# Y9A_4.net
KiCad netlist of a schematic drawn in Altium Designer
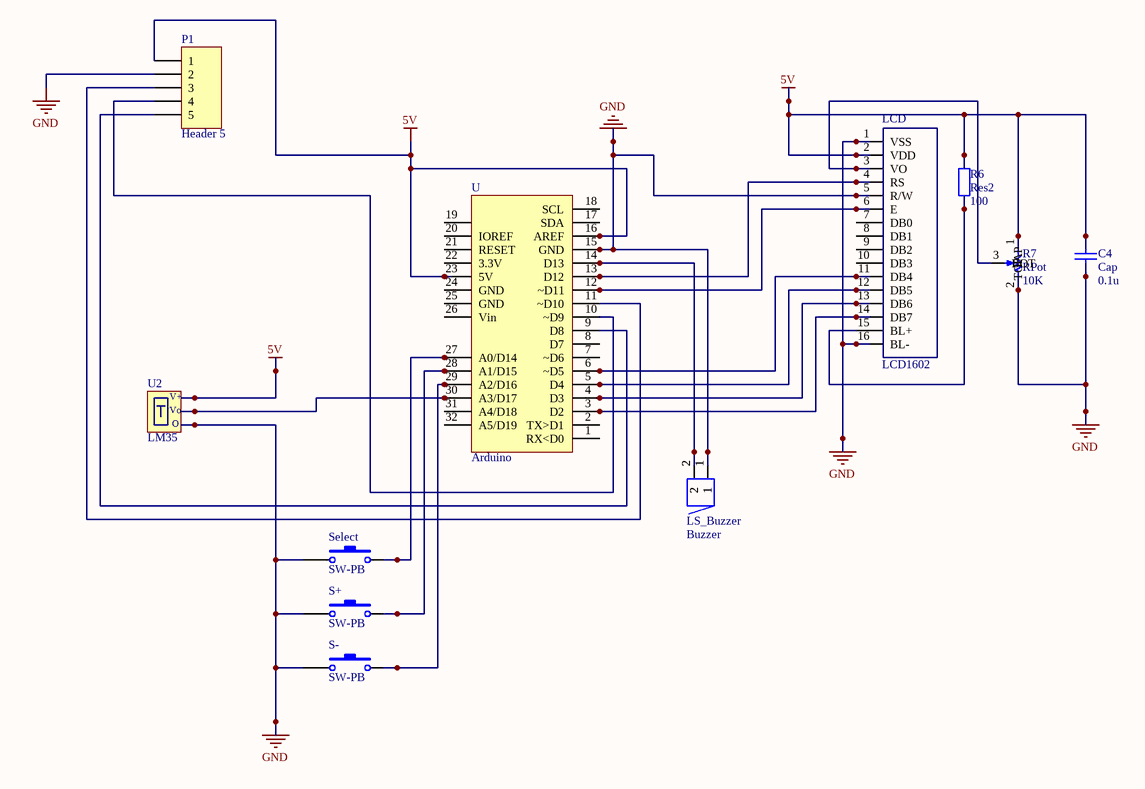
[diagram p0: Y9A_4.SchDoc]

(export (version "E")
  (design (tool "Eeschema 10.0.6"))
  (components
    (comp (ref "C4")
      (value "Cap")
      (footprint "RAD-0.3")
      (description "Capacitor")
      (fields (field (name "ALTIUM_VALUE") "0.1u") (field (name "PUBLISHER") "Altium Limited"))
      (libsource (lib "Miscellaneous Devices") (part "Cap"))
    )
    (comp (ref "LCD") (value "LCD1602") (footprint "LCD1602") (libsource (lib "LCD") (part "LCD1602")))
    (comp (ref "LS_Buzzer")
      (value "Buzzer")
      (footprint "Buzzer")
      (description "Magnetic Transducer Buzzer")
      (fields (field (name "PUBLISHER") "Altium Limited"))
      (libsource (lib "Miscellaneous Devices") (part "Buzzer"))
    )
    (comp (ref "P1")
      (value "Header 5")
      (footprint "HDR1X5")
      (description "Header, 5-Pin")
      (fields (field (name "PUBLISHER") "Altium Limited"))
      (libsource (lib "Miscellaneous Connectors") (part "Header 5"))
    )
    (comp (ref "R6")
      (value "Res2")
      (footprint "AXIAL-0.4")
      (description "Resistor")
      (fields (field (name "ALTIUM_VALUE") "100") (field (name "PUBLISHER") "Altium Limited"))
      (libsource (lib "Miscellaneous Devices") (part "Res2"))
    )
    (comp (ref "R7")
      (value "RPot")
      (footprint "RP-W")
      (description "Potentiometer")
      (fields (field (name "ALTIUM_VALUE") "10K") (field (name "PUBLISHER") "Altium Limited"))
      (libsource (lib "Miscellaneous Devices") (part "RPot"))
    )
    (comp (ref "S+")
      (value "SW-PB")
      (footprint "AN-S")
      (description "Switch")
      (fields (field (name "PUBLISHER") "Altium Limited"))
      (libsource (lib "Miscellaneous Devices") (part "SW-PB"))
    )
    (comp (ref "S-")
      (value "SW-PB")
      (footprint "AN-S")
      (description "Switch")
      (fields (field (name "PUBLISHER") "Altium Limited"))
      (libsource (lib "Miscellaneous Devices") (part "SW-PB"))
    )
    (comp (ref "Select")
      (value "SW-PB")
      (footprint "AN-S")
      (description "Switch")
      (fields (field (name "PUBLISHER") "Altium Limited"))
      (libsource (lib "Miscellaneous Devices") (part "SW-PB"))
    )
    (comp (ref "U")
      (value "Arduino")
      (footprint "Arduino-UNO-EX")
      (libsource (lib "LixhSch-N") (part "Arduino-UNO-EX"))
    )
    (comp (ref "U2")
      (value "LM35")
      (footprint "LM35")
      (description "LM35温度传感器")
      (libsource (lib "LixhSch") (part "LM35"))
    )
  )
  (nets
    (net (code "1") (name "5V") (class "Default")
      (node (ref "C4") (pin "2") (pinfunction "2_2") (pintype "passive"))
      (node (ref "LCD") (pin "2") (pinfunction "VDD_2") (pintype "passive"))
      (node (ref "P1") (pin "1") (pinfunction "1_1") (pintype "passive"))
      (node (ref "R6") (pin "2") (pinfunction "2_2") (pintype "passive"))
      (node (ref "R7") (pin "1") (pinfunction "TOP_1") (pintype "passive"))
      (node (ref "U") (pin "16") (pinfunction "AREF_16") (pintype "power_in"))
      (node (ref "U") (pin "23") (pinfunction "5V_23") (pintype "power_in"))
      (node (ref "U2") (pin "1") (pinfunction "1_1") (pintype "power_in"))
    )
    (net (code "2") (name "GND") (class "Default")
      (node (ref "C4") (pin "1") (pinfunction "1_1") (pintype "passive"))
      (node (ref "LCD") (pin "1") (pinfunction "VSS_1") (pintype "passive"))
      (node (ref "LCD") (pin "16") (pinfunction "BL-_16") (pintype "passive"))
      (node (ref "LCD") (pin "5") (pinfunction "R/W_5") (pintype "passive"))
      (node (ref "LS_Buzzer") (pin "1") (pinfunction "1_1") (pintype "passive"))
      (node (ref "P1") (pin "2") (pinfunction "2_2") (pintype "passive"))
      (node (ref "R7") (pin "2") (pinfunction "TAP_2") (pintype "passive"))
      (node (ref "S+") (pin "1") (pinfunction "1_1") (pintype "passive"))
      (node (ref "S-") (pin "1") (pinfunction "1_1") (pintype "passive"))
      (node (ref "Select") (pin "1") (pinfunction "1_1") (pintype "passive"))
      (node (ref "U") (pin "15") (pinfunction "GND_15") (pintype "power_in"))
      (node (ref "U2") (pin "3") (pinfunction "3_3") (pintype "power_in"))
    )
    (net (code "3") (name "Net-(LCD-BL+)") (class "Default")
      (node (ref "LCD") (pin "15") (pinfunction "BL+_15") (pintype "passive"))
      (node (ref "R6") (pin "1") (pinfunction "1_1") (pintype "passive"))
    )
    (net (code "4") (name "Net-(LCD-DB4)") (class "Default")
      (node (ref "LCD") (pin "11") (pinfunction "DB4_11") (pintype "passive"))
      (node (ref "U") (pin "6") (pinfunction "~D5_6") (pintype "power_in"))
    )
    (net (code "5") (name "Net-(LCD-DB5)") (class "Default")
      (node (ref "LCD") (pin "12") (pinfunction "DB5_12") (pintype "passive"))
      (node (ref "U") (pin "5") (pinfunction "D4_5") (pintype "power_in"))
    )
    (net (code "6") (name "Net-(LCD-DB6)") (class "Default")
      (node (ref "LCD") (pin "13") (pinfunction "DB6_13") (pintype "passive"))
      (node (ref "U") (pin "4") (pinfunction "D3_4") (pintype "power_in"))
    )
    (net (code "7") (name "Net-(LCD-DB7)") (class "Default")
      (node (ref "LCD") (pin "14") (pinfunction "DB7_14") (pintype "passive"))
      (node (ref "U") (pin "3") (pinfunction "D2_3") (pintype "power_in"))
    )
    (net (code "8") (name "Net-(LCD-E)") (class "Default")
      (node (ref "LCD") (pin "6") (pinfunction "E_6") (pintype "passive"))
      (node (ref "U") (pin "12") (pinfunction "~D11_12") (pintype "power_in"))
    )
    (net (code "9") (name "Net-(LCD-RS)") (class "Default")
      (node (ref "LCD") (pin "4") (pinfunction "RS_4") (pintype "passive"))
      (node (ref "U") (pin "13") (pinfunction "D12_13") (pintype "power_in"))
    )
    (net (code "10") (name "Net-(LCD-VO)") (class "Default")
      (node (ref "LCD") (pin "3") (pinfunction "VO_3") (pintype "passive"))
      (node (ref "R7") (pin "3") (pinfunction "BOT_3") (pintype "passive"))
    )
    (net (code "11") (name "Net-(U-A0{slash}D14)") (class "Default")
      (node (ref "Select") (pin "2") (pinfunction "2_2") (pintype "passive"))
      (node (ref "U") (pin "27") (pinfunction "A0/D14_27") (pintype "power_in"))
    )
    (net (code "12") (name "Net-(U-A1{slash}D15)") (class "Default")
      (node (ref "S+") (pin "2") (pinfunction "2_2") (pintype "passive"))
      (node (ref "U") (pin "28") (pinfunction "A1/D15_28") (pintype "power_in"))
    )
    (net (code "13") (name "Net-(U-A2{slash}D16)") (class "Default")
      (node (ref "S-") (pin "2") (pinfunction "2_2") (pintype "passive"))
      (node (ref "U") (pin "29") (pinfunction "A2/D16_29") (pintype "power_in"))
    )
    (net (code "14") (name "Net-(U-A3{slash}D17)") (class "Default")
      (node (ref "U") (pin "30") (pinfunction "A3/D17_30") (pintype "power_in"))
      (node (ref "U2") (pin "2") (pinfunction "2_2") (pintype "passive"))
    )
    (net (code "15") (name "Net-(U-D8)") (class "Default")
      (node (ref "P1") (pin "5") (pinfunction "5_5") (pintype "passive"))
      (node (ref "U") (pin "9") (pinfunction "D8_9") (pintype "power_in"))
    )
    (net (code "16") (name "Net-(U-D13)") (class "Default")
      (node (ref "LS_Buzzer") (pin "2") (pinfunction "2_2") (pintype "passive"))
      (node (ref "U") (pin "14") (pinfunction "D13_14") (pintype "power_in"))
    )
    (net (code "17") (name "Net-(U-~D9)") (class "Default")
      (node (ref "P1") (pin "4") (pinfunction "4_4") (pintype "passive"))
      (node (ref "U") (pin "10") (pinfunction "~D9_10") (pintype "power_in"))
    )
    (net (code "18") (name "Net-(U-~D10)") (class "Default")
      (node (ref "P1") (pin "3") (pinfunction "3_3") (pintype "passive"))
      (node (ref "U") (pin "11") (pinfunction "~D10_11") (pintype "power_in"))
    )
    (net (code "19") (name "unconnected-(LCD-DB0-Pad7)") (class "Default")
      (node (ref "LCD") (pin "7") (pinfunction "DB0_7") (pintype "passive"))
    )
    (net (code "20") (name "unconnected-(LCD-DB1-Pad8)") (class "Default")
      (node (ref "LCD") (pin "8") (pinfunction "DB1_8") (pintype "passive"))
    )
    (net (code "21") (name "unconnected-(LCD-DB2-Pad9)") (class "Default")
      (node (ref "LCD") (pin "9") (pinfunction "DB2_9") (pintype "passive"))
    )
    (net (code "22") (name "unconnected-(LCD-DB3-Pad10)") (class "Default")
      (node (ref "LCD") (pin "10") (pinfunction "DB3_10") (pintype "passive"))
    )
    (net (code "23") (name "unconnected-(U-3.3V-Pad22)") (class "Default")
      (node (ref "U") (pin "22") (pinfunction "3.3V_22") (pintype "power_in"))
    )
    (net (code "24") (name "unconnected-(U-A4{slash}D18-Pad31)") (class "Default")
      (node (ref "U") (pin "31") (pinfunction "A4/D18_31") (pintype "power_in"))
    )
    (net (code "25") (name "unconnected-(U-A5{slash}D19-Pad32)") (class "Default")
      (node (ref "U") (pin "32") (pinfunction "A5/D19_32") (pintype "power_in"))
    )
    (net (code "26") (name "unconnected-(U-D7-Pad8)") (class "Default")
      (node (ref "U") (pin "8") (pinfunction "D7_8") (pintype "power_in"))
    )
    (net (code "27") (name "unconnected-(U-GND-Pad24)") (class "Default")
      (node (ref "U") (pin "24") (pinfunction "GND_24") (pintype "power_in"))
    )
    (net (code "28") (name "unconnected-(U-GND-Pad25)") (class "Default")
      (node (ref "U") (pin "25") (pinfunction "GND_25") (pintype "power_in"))
    )
    (net (code "29") (name "unconnected-(U-IOREF-Pad20)") (class "Default")
      (node (ref "U") (pin "20") (pinfunction "IOREF_20") (pintype "power_in"))
    )
    (net (code "30") (name "unconnected-(U-Pad19)") (class "Default")
      (node (ref "U") (pin "19") (pintype "power_in"))
    )
    (net (code "31") (name "unconnected-(U-RESET-Pad21)") (class "Default")
      (node (ref "U") (pin "21") (pinfunction "RESET_21") (pintype "power_in"))
    )
    (net (code "32") (name "unconnected-(U-RX<D0-Pad1)") (class "Default")
      (node (ref "U") (pin "1") (pinfunction "RX<D0_1") (pintype "power_in"))
    )
    (net (code "33") (name "unconnected-(U-SCL-Pad18)") (class "Default")
      (node (ref "U") (pin "18") (pinfunction "SCL_18") (pintype "power_in"))
    )
    (net (code "34") (name "unconnected-(U-SDA-Pad17)") (class "Default")
      (node (ref "U") (pin "17") (pinfunction "SDA_17") (pintype "power_in"))
    )
    (net (code "35") (name "unconnected-(U-TX>D1-Pad2)") (class "Default")
      (node (ref "U") (pin "2") (pinfunction "TX>D1_2") (pintype "power_in"))
    )
    (net (code "36") (name "unconnected-(U-Vin-Pad26)") (class "Default")
      (node (ref "U") (pin "26") (pinfunction "Vin_26") (pintype "power_in"))
    )
    (net (code "37") (name "unconnected-(U-~D6-Pad7)") (class "Default")
      (node (ref "U") (pin "7") (pinfunction "~D6_7") (pintype "power_in"))
    )
  )
)
